# HV_Power_Supply.net
KiCad netlist of a schematic drawn in Altium Designer
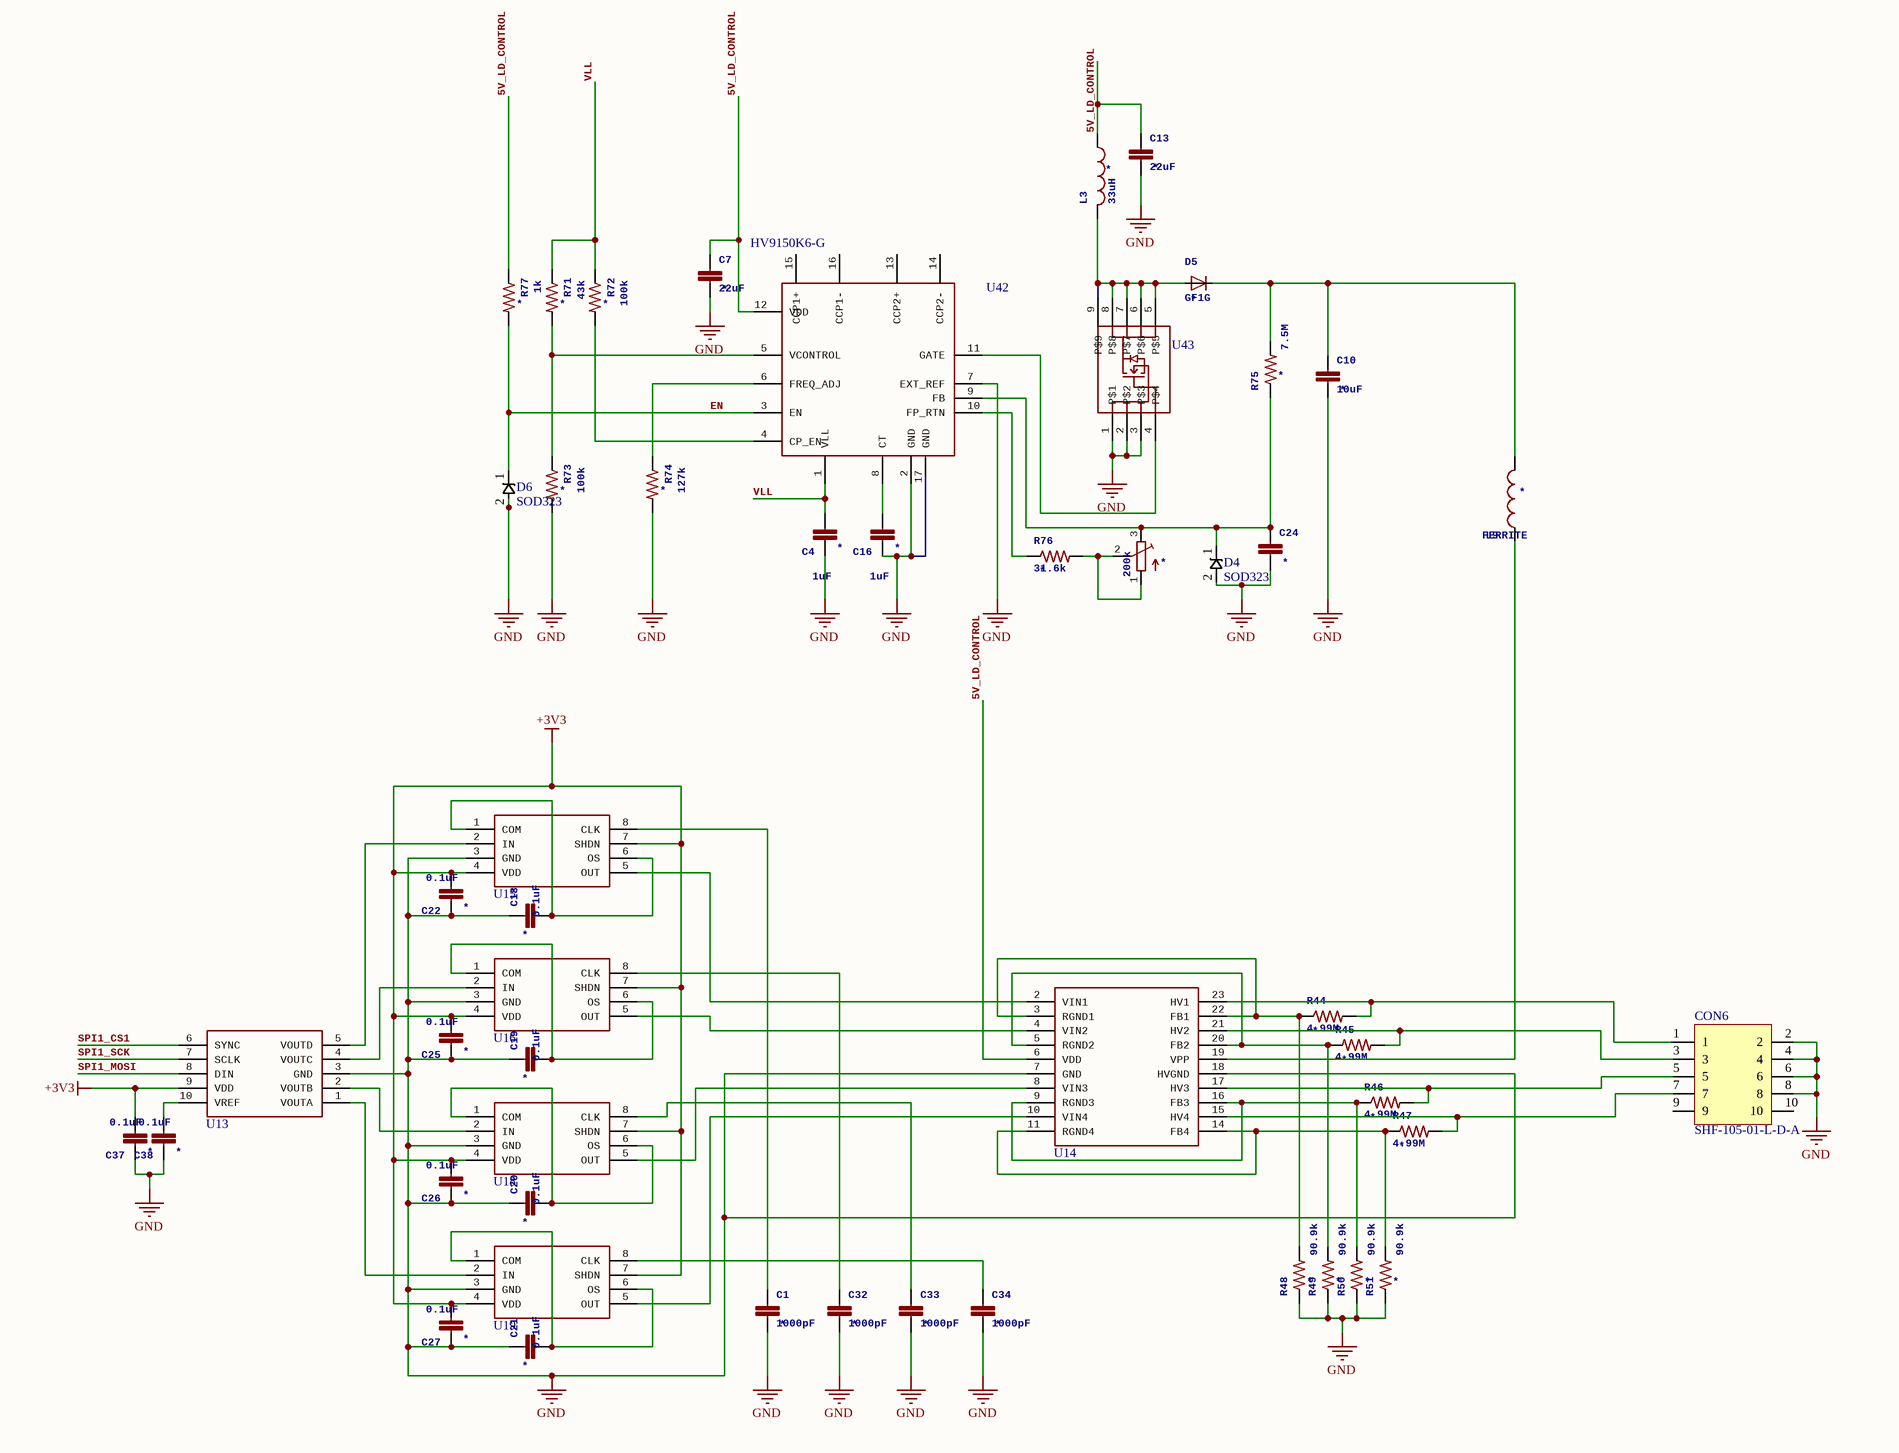
[diagram p0: HV Power Supply.SchDoc]

(export (version "E")
  (design (tool "Eeschema 10.0.6"))
  (components
    (comp (ref "C1")
      (value "1000pF")
      (footprint "0402 B")
      (description "0402 (1005 Metric) Nick Garner - TeleSense")
      (fields (field (name "NAME") "*") (field (name "LIBRARYNAME") "Perfect_0402"))
      (libsource (lib "") (part "CAP_0402_1"))
    )
    (comp (ref "C4")
      (value "1uF")
      (footprint "0603")
      (description "CAPACITOR, European symbol")
      (fields (field (name "NAME") "*"))
      (libsource (lib "") (part "C-EUC0603_1"))
    )
    (comp (ref "C7")
      (value "22uF")
      (footprint "0603")
      (description "CAPACITOR, European symbol")
      (fields (field (name "NAME") "*"))
      (libsource (lib "rcl") (part "C-EUC0603"))
    )
    (comp (ref "C10")
      (value "10uF")
      (footprint "C1812")
      (description "CAPACITOR, European symbol")
      (fields (field (name "NAME") "*"))
      (libsource (lib "rcl") (part "C-EUC1812"))
    )
    (comp (ref "C13")
      (value "22uF")
      (footprint "0603")
      (description "CAPACITOR, European symbol")
      (fields (field (name "NAME") "*"))
      (libsource (lib "rcl") (part "C-EUC0603"))
    )
    (comp (ref "C16")
      (value "1uF")
      (footprint "0603")
      (description "CAPACITOR, European symbol")
      (fields (field (name "NAME") "*"))
      (libsource (lib "") (part "C-EUC0603_1"))
    )
    (comp (ref "C18")
      (value "0.1uF")
      (footprint "0402 B")
      (description "0402 (1005 Metric) Nick Garner - TeleSense")
      (fields (field (name "NAME") "*") (field (name "LIBRARYNAME") "Perfect_0402"))
      (libsource (lib "") (part "CAP_0402_2"))
    )
    (comp (ref "C19")
      (value "0.1uF")
      (footprint "0402 B")
      (description "0402 (1005 Metric) Nick Garner - TeleSense")
      (fields (field (name "NAME") "*") (field (name "LIBRARYNAME") "Perfect_0402"))
      (libsource (lib "") (part "CAP_0402_2"))
    )
    (comp (ref "C20")
      (value "0.1uF")
      (footprint "0402 B")
      (description "0402 (1005 Metric) Nick Garner - TeleSense")
      (fields (field (name "NAME") "*") (field (name "LIBRARYNAME") "Perfect_0402"))
      (libsource (lib "") (part "CAP_0402_2"))
    )
    (comp (ref "C21")
      (value "0.1uF")
      (footprint "0402 B")
      (description "0402 (1005 Metric) Nick Garner - TeleSense")
      (fields (field (name "NAME") "*") (field (name "LIBRARYNAME") "Perfect_0402"))
      (libsource (lib "") (part "CAP_0402_2"))
    )
    (comp (ref "C22")
      (value "0.1uF")
      (footprint "0402 B")
      (description "0402 (1005 Metric) Nick Garner - TeleSense")
      (fields (field (name "NAME") "*") (field (name "LIBRARYNAME") "Perfect_0402"))
      (libsource (lib "Perfect_0402") (part "CAP_0402"))
    )
    (comp (ref "C24")
      (value "C-EUC0603")
      (footprint "0603")
      (description "CAPACITOR, European symbol")
      (fields (field (name "NAME") "*"))
      (libsource (lib "rcl") (part "C-EUC0603"))
    )
    (comp (ref "C25")
      (value "0.1uF")
      (footprint "0402 B")
      (description "0402 (1005 Metric) Nick Garner - TeleSense")
      (fields (field (name "NAME") "*") (field (name "LIBRARYNAME") "Perfect_0402"))
      (libsource (lib "Perfect_0402") (part "CAP_0402"))
    )
    (comp (ref "C26")
      (value "0.1uF")
      (footprint "0402 B")
      (description "0402 (1005 Metric) Nick Garner - TeleSense")
      (fields (field (name "NAME") "*") (field (name "LIBRARYNAME") "Perfect_0402"))
      (libsource (lib "Perfect_0402") (part "CAP_0402"))
    )
    (comp (ref "C27")
      (value "0.1uF")
      (footprint "0402 B")
      (description "0402 (1005 Metric) Nick Garner - TeleSense")
      (fields (field (name "NAME") "*") (field (name "LIBRARYNAME") "Perfect_0402"))
      (libsource (lib "Perfect_0402") (part "CAP_0402"))
    )
    (comp (ref "C32")
      (value "1000pF")
      (footprint "0402 B")
      (description "0402 (1005 Metric) Nick Garner - TeleSense")
      (fields (field (name "NAME") "*") (field (name "LIBRARYNAME") "Perfect_0402"))
      (libsource (lib "") (part "CAP_0402_1"))
    )
    (comp (ref "C33")
      (value "1000pF")
      (footprint "0402 B")
      (description "0402 (1005 Metric) Nick Garner - TeleSense")
      (fields (field (name "NAME") "*") (field (name "LIBRARYNAME") "Perfect_0402"))
      (libsource (lib "") (part "CAP_0402_1"))
    )
    (comp (ref "C34")
      (value "1000pF")
      (footprint "0402 B")
      (description "0402 (1005 Metric) Nick Garner - TeleSense")
      (fields (field (name "NAME") "*") (field (name "LIBRARYNAME") "Perfect_0402"))
      (libsource (lib "") (part "CAP_0402_1"))
    )
    (comp (ref "C37")
      (value "0.1uF")
      (footprint "0402 B")
      (description "0402 (1005 Metric) Nick Garner - TeleSense")
      (fields (field (name "NAME") "*") (field (name "LIBRARYNAME") "Perfect_0402"))
      (libsource (lib "Perfect_0402") (part "CAP_0402"))
    )
    (comp (ref "C38")
      (value "0.1uF")
      (footprint "0402 B")
      (description "0402 (1005 Metric) Nick Garner - TeleSense")
      (fields (field (name "NAME") "*") (field (name "LIBRARYNAME") "Perfect_0402"))
      (libsource (lib "Perfect_0402") (part "CAP_0402"))
    )
    (comp (ref "CON6")
      (value "SHF-105-01-L-D-A")
      (footprint "SHF-105-01-L-D-RA")
      (libsource (lib "DaughterBoard") (part "SHF-105-01-L-D-A"))
    )
    (comp (ref "D4") (value "SOD323") (footprint "SOD-323") (libsource (lib "DaughterBoard") (part "SOD323")))
    (comp (ref "D5")
      (value "GF1G")
      (footprint "DO-214BA")
      (description "DIODE")
      (fields (field (name "NAME") "*"))
      (libsource (lib "diode") (part "GF1"))
    )
    (comp (ref "D6") (value "SOD323") (footprint "SOD-323") (libsource (lib "DaughterBoard") (part "SOD323")))
    (comp (ref "L3")
      (value "33uH")
      (footprint "L1812")
      (description "INDUCTOR, American symbol")
      (fields (field (name "NAME") "*"))
      (libsource (lib "resistor") (part "L-USL1812"))
    )
    (comp (ref "L9")
      (value "FERRITE")
      (footprint "0603")
      (fields (field (name "NAME") "*"))
      (libsource (lib "SparkFun-Passives") (part "INDUCTOR30OHM,1.8A"))
    )
    (comp (ref "R44")
      (value "4.99M")
      (footprint "0603R")
      (description "RESISTOR, American symbol")
      (fields (field (name "NAME") "*"))
      (libsource (lib "rcl") (part "R-US_R0603"))
    )
    (comp (ref "R45")
      (value "4.99M")
      (footprint "0603R")
      (description "RESISTOR, American symbol")
      (fields (field (name "NAME") "*"))
      (libsource (lib "rcl") (part "R-US_R0603"))
    )
    (comp (ref "R46")
      (value "4.99M")
      (footprint "0603R")
      (description "RESISTOR, American symbol")
      (fields (field (name "NAME") "*"))
      (libsource (lib "rcl") (part "R-US_R0603"))
    )
    (comp (ref "R47")
      (value "4.99M")
      (footprint "0603R")
      (description "RESISTOR, American symbol")
      (fields (field (name "NAME") "*"))
      (libsource (lib "rcl") (part "R-US_R0603"))
    )
    (comp (ref "R48")
      (value "90.9k")
      (footprint "0603R")
      (description "RESISTOR, American symbol")
      (fields (field (name "NAME") "*"))
      (libsource (lib "rcl") (part "R-US_R0603"))
    )
    (comp (ref "R49")
      (value "90.9k")
      (footprint "0603R")
      (description "RESISTOR, American symbol")
      (fields (field (name "NAME") "*"))
      (libsource (lib "rcl") (part "R-US_R0603"))
    )
    (comp (ref "R50")
      (value "90.9k")
      (footprint "0603R")
      (description "RESISTOR, American symbol")
      (fields (field (name "NAME") "*"))
      (libsource (lib "rcl") (part "R-US_R0603"))
    )
    (comp (ref "R51")
      (value "90.9k")
      (footprint "0603R")
      (description "RESISTOR, American symbol")
      (fields (field (name "NAME") "*"))
      (libsource (lib "rcl") (part "R-US_R0603"))
    )
    (comp (ref "R71")
      (value "43k")
      (footprint "0603R")
      (description "RESISTOR, American symbol")
      (fields (field (name "NAME") "*"))
      (libsource (lib "rcl") (part "R-US_R0603"))
    )
    (comp (ref "R72")
      (value "100k")
      (footprint "0603R")
      (description "RESISTOR, American symbol")
      (fields (field (name "NAME") "*"))
      (libsource (lib "rcl") (part "R-US_R0603"))
    )
    (comp (ref "R73")
      (value "100k")
      (footprint "0603R")
      (description "RESISTOR, American symbol")
      (fields (field (name "NAME") "*"))
      (libsource (lib "rcl") (part "R-US_R0603"))
    )
    (comp (ref "R74")
      (value "127k")
      (footprint "0603R")
      (description "RESISTOR, American symbol")
      (fields (field (name "NAME") "*"))
      (libsource (lib "rcl") (part "R-US_R0603"))
    )
    (comp (ref "R75")
      (value "7.5M")
      (footprint "1206R")
      (description "RESISTOR, American symbol")
      (fields (field (name "NAME") "*"))
      (libsource (lib "rcl") (part "R-US_R1206"))
    )
    (comp (ref "R76")
      (value "31.6k")
      (footprint "0603R")
      (description "RESISTOR, American symbol")
      (fields (field (name "NAME") "*"))
      (libsource (lib "rcl") (part "R-US_R0603"))
    )
    (comp (ref "R77")
      (value "1k")
      (footprint "0603R")
      (description "RESISTOR, American symbol")
      (fields (field (name "NAME") "*"))
      (libsource (lib "rcl") (part "R-US_R0603"))
    )
    (comp (ref "U13") (value "AD5664R") (footprint "MSOP-10") (libsource (lib "custom") (part "AD5664R")))
    (comp (ref "U14") (value "HV264TS-G") (footprint "TSSOP-24") (libsource (lib "custom") (part "HV264")))
    (comp (ref "U15") (value "MAX7413") (footprint "uMAX-8") (libsource (lib "custom") (part "MAX7413")))
    (comp (ref "U16") (value "MAX7413") (footprint "uMAX-8") (libsource (lib "custom") (part "MAX7413")))
    (comp (ref "U18") (value "MAX7413") (footprint "uMAX-8") (libsource (lib "custom") (part "MAX7413")))
    (comp (ref "U19") (value "MAX7413") (footprint "uMAX-8") (libsource (lib "custom") (part "MAX7413")))
    (comp (ref "U42") (value "HV9150K6-G") (footprint "QFN-16") (libsource (lib "custom") (part "HV9150")))
    (comp (ref "U43")
      (value "BSZ42DN25NS3GATMA1")
      (footprint "TDSON-8")
      (libsource (lib "custom") (part "BSZ42DN25NS3"))
    )
    (comp (ref "U44")
      (value "200k")
      (footprint "TC33X")
      (description "SMT trimmer potentiometer part number TC33X http://www.ladyada.net/library/eagle")
      (fields (field (name "NAME") "*"))
      (libsource (lib "adafruit") (part "TRIMPOTTC33X"))
    )
  )
  (nets
    (net (code "1") (name "+3V3") (class "Default")
      (node (ref "C22") (pin "2") (pinfunction "2_2") (pintype "passive"))
      (node (ref "C25") (pin "2") (pinfunction "2_2") (pintype "passive"))
      (node (ref "C26") (pin "2") (pinfunction "2_2") (pintype "passive"))
      (node (ref "C27") (pin "2") (pinfunction "2_2") (pintype "passive"))
      (node (ref "C37") (pin "2") (pinfunction "2_2") (pintype "passive"))
      (node (ref "U13") (pin "9") (pinfunction "VDD_9") (pintype "passive"))
      (node (ref "U15") (pin "4") (pinfunction "VDD_4") (pintype "passive"))
      (node (ref "U15") (pin "7") (pinfunction "SHDN_7") (pintype "passive"))
      (node (ref "U16") (pin "4") (pinfunction "VDD_4") (pintype "passive"))
      (node (ref "U16") (pin "7") (pinfunction "SHDN_7") (pintype "passive"))
      (node (ref "U18") (pin "4") (pinfunction "VDD_4") (pintype "passive"))
      (node (ref "U18") (pin "7") (pinfunction "SHDN_7") (pintype "passive"))
      (node (ref "U19") (pin "4") (pinfunction "VDD_4") (pintype "passive"))
      (node (ref "U19") (pin "7") (pinfunction "SHDN_7") (pintype "passive"))
    )
    (net (code "2") (name "/5V_LD_CONTROL") (class "Default")
      (node (ref "C13") (pin "1") (pinfunction "1_1") (pintype "passive"))
      (node (ref "C7") (pin "1") (pinfunction "1_1") (pintype "passive"))
      (node (ref "L3") (pin "1") (pinfunction "1_1") (pintype "passive"))
      (node (ref "R77") (pin "1") (pinfunction "1_1") (pintype "passive"))
      (node (ref "U14") (pin "6") (pinfunction "VDD_6") (pintype "passive"))
      (node (ref "U42") (pin "12") (pinfunction "VDD_12") (pintype "passive"))
    )
    (net (code "3") (name "/EN") (class "Default")
      (node (ref "D6") (pin "1") (pinfunction "31_1") (pintype "passive"))
      (node (ref "R77") (pin "2") (pinfunction "2_2") (pintype "passive"))
      (node (ref "U42") (pin "3") (pinfunction "EN_3") (pintype "passive"))
    )
    (net (code "4") (name "/SPI1_CS1") (class "Default")
      (node (ref "U13") (pin "6") (pinfunction "SYNC_6") (pintype "passive"))
    )
    (net (code "5") (name "/SPI1_MOSI") (class "Default")
      (node (ref "U13") (pin "8") (pinfunction "DIN_8") (pintype "passive"))
    )
    (net (code "6") (name "/SPI1_SCK") (class "Default")
      (node (ref "U13") (pin "7") (pinfunction "SCLK_7") (pintype "passive"))
    )
    (net (code "7") (name "/VLL") (class "Default")
      (node (ref "C4") (pin "2") (pinfunction "2_2") (pintype "passive"))
      (node (ref "R71") (pin "1") (pinfunction "1_1") (pintype "passive"))
      (node (ref "R72") (pin "1") (pinfunction "1_1") (pintype "passive"))
      (node (ref "U42") (pin "1") (pinfunction "VLL_1") (pintype "passive"))
    )
    (net (code "8") (name "GND") (class "Default")
      (node (ref "C1") (pin "2") (pinfunction "2_2") (pintype "passive"))
      (node (ref "C10") (pin "2") (pinfunction "2_2") (pintype "passive"))
      (node (ref "C13") (pin "2") (pinfunction "2_2") (pintype "passive"))
      (node (ref "C16") (pin "1") (pinfunction "1_1") (pintype "passive"))
      (node (ref "C18") (pin "1") (pinfunction "1_1") (pintype "passive"))
      (node (ref "C19") (pin "1") (pinfunction "1_1") (pintype "passive"))
      (node (ref "C20") (pin "1") (pinfunction "1_1") (pintype "passive"))
      (node (ref "C21") (pin "1") (pinfunction "1_1") (pintype "passive"))
      (node (ref "C22") (pin "1") (pinfunction "1_1") (pintype "passive"))
      (node (ref "C24") (pin "2") (pinfunction "2_2") (pintype "passive"))
      (node (ref "C25") (pin "1") (pinfunction "1_1") (pintype "passive"))
      (node (ref "C26") (pin "1") (pinfunction "1_1") (pintype "passive"))
      (node (ref "C27") (pin "1") (pinfunction "1_1") (pintype "passive"))
      (node (ref "C32") (pin "2") (pinfunction "2_2") (pintype "passive"))
      (node (ref "C33") (pin "2") (pinfunction "2_2") (pintype "passive"))
      (node (ref "C34") (pin "2") (pinfunction "2_2") (pintype "passive"))
      (node (ref "C37") (pin "1") (pinfunction "1_1") (pintype "passive"))
      (node (ref "C38") (pin "1") (pinfunction "1_1") (pintype "passive"))
      (node (ref "C4") (pin "1") (pinfunction "1_1") (pintype "passive"))
      (node (ref "C7") (pin "2") (pinfunction "2_2") (pintype "passive"))
      (node (ref "CON6") (pin "2") (pinfunction "2_2") (pintype "passive"))
      (node (ref "CON6") (pin "4") (pinfunction "4_4") (pintype "passive"))
      (node (ref "CON6") (pin "6") (pinfunction "6_6") (pintype "passive"))
      (node (ref "CON6") (pin "8") (pinfunction "8_8") (pintype "passive"))
      (node (ref "D4") (pin "2") (pinfunction "32_2") (pintype "passive"))
      (node (ref "D6") (pin "2") (pinfunction "32_2") (pintype "passive"))
      (node (ref "R48") (pin "1") (pinfunction "1_1") (pintype "passive"))
      (node (ref "R49") (pin "1") (pinfunction "1_1") (pintype "passive"))
      (node (ref "R50") (pin "1") (pinfunction "1_1") (pintype "passive"))
      (node (ref "R51") (pin "1") (pinfunction "1_1") (pintype "passive"))
      (node (ref "R73") (pin "2") (pinfunction "2_2") (pintype "passive"))
      (node (ref "R74") (pin "2") (pinfunction "2_2") (pintype "passive"))
      (node (ref "U13") (pin "3") (pinfunction "GND_3") (pintype "passive"))
      (node (ref "U14") (pin "18") (pinfunction "HVGND_18") (pintype "passive"))
      (node (ref "U14") (pin "7") (pinfunction "GND_7") (pintype "passive"))
      (node (ref "U15") (pin "3") (pinfunction "GND_3") (pintype "passive"))
      (node (ref "U16") (pin "3") (pinfunction "GND_3") (pintype "passive"))
      (node (ref "U18") (pin "3") (pinfunction "GND_3") (pintype "passive"))
      (node (ref "U19") (pin "3") (pinfunction "GND_3") (pintype "passive"))
      (node (ref "U42") (pin "17") (pinfunction "GND_17") (pintype "passive"))
      (node (ref "U42") (pin "2") (pinfunction "GND_2") (pintype "passive"))
      (node (ref "U42") (pin "7") (pinfunction "EXT_REF_7") (pintype "passive"))
      (node (ref "U43") (pin "1") (pinfunction "P$1_1") (pintype "passive"))
      (node (ref "U43") (pin "2") (pinfunction "P$2_2") (pintype "passive"))
      (node (ref "U43") (pin "3") (pinfunction "P$3_3") (pintype "passive"))
    )
    (net (code "9") (name "Net-(C10-Pad1)") (class "Default")
      (node (ref "C10") (pin "1") (pinfunction "1_1") (pintype "passive"))
      (node (ref "D5") (pin "2") (pinfunction "2_2") (pintype "passive"))
      (node (ref "L9") (pin "2") (pinfunction "2_2") (pintype "passive"))
      (node (ref "R75") (pin "2") (pinfunction "2_2") (pintype "passive"))
    )
    (net (code "10") (name "Net-(D4-31)") (class "Default")
      (node (ref "C24") (pin "1") (pinfunction "1_1") (pintype "passive"))
      (node (ref "D4") (pin "1") (pinfunction "31_1") (pintype "passive"))
      (node (ref "R75") (pin "1") (pinfunction "1_1") (pintype "passive"))
      (node (ref "U42") (pin "9") (pinfunction "FB_9") (pintype "passive"))
      (node (ref "U44") (pin "3") (pinfunction "E_3") (pintype "passive"))
    )
    (net (code "11") (name "Net-(U13-VOUTA)") (class "Default")
      (node (ref "U13") (pin "1") (pinfunction "VOUTA_1") (pintype "passive"))
      (node (ref "U19") (pin "2") (pinfunction "IN_2") (pintype "passive"))
    )
    (net (code "12") (name "Net-(U13-VOUTB)") (class "Default")
      (node (ref "U13") (pin "2") (pinfunction "VOUTB_2") (pintype "passive"))
      (node (ref "U18") (pin "2") (pinfunction "IN_2") (pintype "passive"))
    )
    (net (code "13") (name "Net-(U13-VOUTC)") (class "Default")
      (node (ref "U13") (pin "4") (pinfunction "VOUTC_4") (pintype "passive"))
      (node (ref "U16") (pin "2") (pinfunction "IN_2") (pintype "passive"))
    )
    (net (code "14") (name "Net-(U13-VOUTD)") (class "Default")
      (node (ref "U13") (pin "5") (pinfunction "VOUTD_5") (pintype "passive"))
      (node (ref "U15") (pin "2") (pinfunction "IN_2") (pintype "passive"))
    )
    (net (code "15") (name "Net-(U13-VREF)") (class "Default")
      (node (ref "C38") (pin "2") (pinfunction "2_2") (pintype "passive"))
      (node (ref "U13") (pin "10") (pinfunction "VREF_10") (pintype "passive"))
    )
    (net (code "16") (name "Net-(U14-FB1)") (class "Default")
      (node (ref "R44") (pin "1") (pinfunction "1_1") (pintype "passive"))
      (node (ref "R48") (pin "2") (pinfunction "2_2") (pintype "passive"))
      (node (ref "U14") (pin "22") (pinfunction "FB1_22") (pintype "passive"))
      (node (ref "U14") (pin "3") (pinfunction "RGND1_3") (pintype "passive"))
    )
    (net (code "17") (name "Net-(U14-FB2)") (class "Default")
      (node (ref "R45") (pin "1") (pinfunction "1_1") (pintype "passive"))
      (node (ref "R49") (pin "2") (pinfunction "2_2") (pintype "passive"))
      (node (ref "U14") (pin "20") (pinfunction "FB2_20") (pintype "passive"))
      (node (ref "U14") (pin "5") (pinfunction "RGND2_5") (pintype "passive"))
    )
    (net (code "18") (name "Net-(U14-FB3)") (class "Default")
      (node (ref "R46") (pin "1") (pinfunction "1_1") (pintype "passive"))
      (node (ref "R50") (pin "2") (pinfunction "2_2") (pintype "passive"))
      (node (ref "U14") (pin "16") (pinfunction "FB3_16") (pintype "passive"))
      (node (ref "U14") (pin "9") (pinfunction "RGND3_9") (pintype "passive"))
    )
    (net (code "19") (name "Net-(U14-FB4)") (class "Default")
      (node (ref "R47") (pin "1") (pinfunction "1_1") (pintype "passive"))
      (node (ref "R51") (pin "2") (pinfunction "2_2") (pintype "passive"))
      (node (ref "U14") (pin "11") (pinfunction "RGND4_11") (pintype "passive"))
      (node (ref "U14") (pin "14") (pinfunction "FB4_14") (pintype "passive"))
    )
    (net (code "20") (name "Net-(U14-HV1)") (class "Default")
      (node (ref "CON6") (pin "1") (pinfunction "1_1") (pintype "passive"))
      (node (ref "R44") (pin "2") (pinfunction "2_2") (pintype "passive"))
      (node (ref "U14") (pin "23") (pinfunction "HV1_23") (pintype "passive"))
    )
    (net (code "21") (name "Net-(U14-HV2)") (class "Default")
      (node (ref "CON6") (pin "3") (pinfunction "3_3") (pintype "passive"))
      (node (ref "R45") (pin "2") (pinfunction "2_2") (pintype "passive"))
      (node (ref "U14") (pin "21") (pinfunction "HV2_21") (pintype "passive"))
    )
    (net (code "22") (name "Net-(U14-HV3)") (class "Default")
      (node (ref "CON6") (pin "5") (pinfunction "5_5") (pintype "passive"))
      (node (ref "R46") (pin "2") (pinfunction "2_2") (pintype "passive"))
      (node (ref "U14") (pin "17") (pinfunction "HV3_17") (pintype "passive"))
    )
    (net (code "23") (name "Net-(U14-HV4)") (class "Default")
      (node (ref "CON6") (pin "7") (pinfunction "7_7") (pintype "passive"))
      (node (ref "R47") (pin "2") (pinfunction "2_2") (pintype "passive"))
      (node (ref "U14") (pin "15") (pinfunction "HV4_15") (pintype "passive"))
    )
    (net (code "24") (name "Net-(U14-VIN1)") (class "Default")
      (node (ref "U14") (pin "2") (pinfunction "VIN1_2") (pintype "passive"))
      (node (ref "U15") (pin "5") (pinfunction "OUT_5") (pintype "passive"))
    )
    (net (code "25") (name "Net-(U14-VIN2)") (class "Default")
      (node (ref "U14") (pin "4") (pinfunction "VIN2_4") (pintype "passive"))
      (node (ref "U16") (pin "5") (pinfunction "OUT_5") (pintype "passive"))
    )
    (net (code "26") (name "Net-(U14-VIN3)") (class "Default")
      (node (ref "U14") (pin "8") (pinfunction "VIN3_8") (pintype "passive"))
      (node (ref "U18") (pin "5") (pinfunction "OUT_5") (pintype "passive"))
    )
    (net (code "27") (name "Net-(U14-VIN4)") (class "Default")
      (node (ref "U14") (pin "10") (pinfunction "VIN4_10") (pintype "passive"))
      (node (ref "U19") (pin "5") (pinfunction "OUT_5") (pintype "passive"))
    )
    (net (code "28") (name "Net-(U14-VPP)") (class "Default")
      (node (ref "L9") (pin "1") (pinfunction "1_1") (pintype "passive"))
      (node (ref "U14") (pin "19") (pinfunction "VPP_19") (pintype "passive"))
    )
    (net (code "29") (name "Net-(U15-CLK)") (class "Default")
      (node (ref "C1") (pin "1") (pinfunction "1_1") (pintype "passive"))
      (node (ref "U15") (pin "8") (pinfunction "CLK_8") (pintype "passive"))
    )
    (net (code "30") (name "Net-(U15-COM)") (class "Default")
      (node (ref "C18") (pin "2") (pinfunction "2_2") (pintype "passive"))
      (node (ref "U15") (pin "1") (pinfunction "COM_1") (pintype "passive"))
      (node (ref "U15") (pin "6") (pinfunction "OS_6") (pintype "passive"))
    )
    (net (code "31") (name "Net-(U16-CLK)") (class "Default")
      (node (ref "C32") (pin "1") (pinfunction "1_1") (pintype "passive"))
      (node (ref "U16") (pin "8") (pinfunction "CLK_8") (pintype "passive"))
    )
    (net (code "32") (name "Net-(U16-COM)") (class "Default")
      (node (ref "C19") (pin "2") (pinfunction "2_2") (pintype "passive"))
      (node (ref "U16") (pin "1") (pinfunction "COM_1") (pintype "passive"))
      (node (ref "U16") (pin "6") (pinfunction "OS_6") (pintype "passive"))
    )
    (net (code "33") (name "Net-(U18-CLK)") (class "Default")
      (node (ref "C33") (pin "1") (pinfunction "1_1") (pintype "passive"))
      (node (ref "U18") (pin "8") (pinfunction "CLK_8") (pintype "passive"))
    )
    (net (code "34") (name "Net-(U18-COM)") (class "Default")
      (node (ref "C20") (pin "2") (pinfunction "2_2") (pintype "passive"))
      (node (ref "U18") (pin "1") (pinfunction "COM_1") (pintype "passive"))
      (node (ref "U18") (pin "6") (pinfunction "OS_6") (pintype "passive"))
    )
    (net (code "35") (name "Net-(U19-CLK)") (class "Default")
      (node (ref "C34") (pin "1") (pinfunction "1_1") (pintype "passive"))
      (node (ref "U19") (pin "8") (pinfunction "CLK_8") (pintype "passive"))
    )
    (net (code "36") (name "Net-(U19-COM)") (class "Default")
      (node (ref "C21") (pin "2") (pinfunction "2_2") (pintype "passive"))
      (node (ref "U19") (pin "1") (pinfunction "COM_1") (pintype "passive"))
      (node (ref "U19") (pin "6") (pinfunction "OS_6") (pintype "passive"))
    )
    (net (code "37") (name "Net-(U42-CP_EN)") (class "Default")
      (node (ref "R72") (pin "2") (pinfunction "2_2") (pintype "passive"))
      (node (ref "U42") (pin "4") (pinfunction "CP_EN_4") (pintype "passive"))
    )
    (net (code "38") (name "Net-(U42-CT)") (class "Default")
      (node (ref "C16") (pin "2") (pinfunction "2_2") (pintype "passive"))
      (node (ref "U42") (pin "8") (pinfunction "CT_8") (pintype "passive"))
    )
    (net (code "39") (name "Net-(U42-FP_RTN)") (class "Default")
      (node (ref "R76") (pin "1") (pinfunction "1_1") (pintype "passive"))
      (node (ref "U42") (pin "10") (pinfunction "FP_RTN_10") (pintype "passive"))
    )
    (net (code "40") (name "Net-(U42-FREQ_ADJ)") (class "Default")
      (node (ref "R74") (pin "1") (pinfunction "1_1") (pintype "passive"))
      (node (ref "U42") (pin "6") (pinfunction "FREQ_ADJ_6") (pintype "passive"))
    )
    (net (code "41") (name "Net-(U42-GATE)") (class "Default")
      (node (ref "U42") (pin "11") (pinfunction "GATE_11") (pintype "passive"))
      (node (ref "U43") (pin "4") (pinfunction "P$4_4") (pintype "passive"))
    )
    (net (code "42") (name "Net-(U42-VCONTROL)") (class "Default")
      (node (ref "R71") (pin "2") (pinfunction "2_2") (pintype "passive"))
      (node (ref "R73") (pin "1") (pinfunction "1_1") (pintype "passive"))
      (node (ref "U42") (pin "5") (pinfunction "VCONTROL_5") (pintype "passive"))
    )
    (net (code "43") (name "Net-(U43-P$5)") (class "Default")
      (node (ref "D5") (pin "1") (pinfunction "1_1") (pintype "passive"))
      (node (ref "L3") (pin "2") (pinfunction "2_2") (pintype "passive"))
      (node (ref "U43") (pin "5") (pinfunction "P$5_5") (pintype "passive"))
      (node (ref "U43") (pin "6") (pinfunction "P$6_6") (pintype "passive"))
      (node (ref "U43") (pin "7") (pinfunction "P$7_7") (pintype "passive"))
      (node (ref "U43") (pin "8") (pinfunction "P$8_8") (pintype "passive"))
      (node (ref "U43") (pin "9") (pinfunction "P$9_9") (pintype "passive"))
    )
    (net (code "44") (name "Net-(U44-A)") (class "Default")
      (node (ref "R76") (pin "2") (pinfunction "2_2") (pintype "passive"))
      (node (ref "U44") (pin "1") (pinfunction "A_1") (pintype "passive"))
      (node (ref "U44") (pin "2") (pinfunction "S_2") (pintype "passive"))
    )
    (net (code "45") (name "unconnected-(CON6-Pad9)") (class "Default")
      (node (ref "CON6") (pin "9") (pinfunction "9_9") (pintype "passive"))
    )
    (net (code "46") (name "unconnected-(CON6-Pad10)") (class "Default")
      (node (ref "CON6") (pin "10") (pinfunction "10_10") (pintype "passive"))
    )
    (net (code "47") (name "unconnected-(U42-CCP1+-Pad15)") (class "Default")
      (node (ref "U42") (pin "15") (pinfunction "CCP1+_15") (pintype "passive"))
    )
    (net (code "48") (name "unconnected-(U42-CCP1--Pad16)") (class "Default")
      (node (ref "U42") (pin "16") (pinfunction "CCP1-_16") (pintype "passive"))
    )
    (net (code "49") (name "unconnected-(U42-CCP2+-Pad13)") (class "Default")
      (node (ref "U42") (pin "13") (pinfunction "CCP2+_13") (pintype "passive"))
    )
    (net (code "50") (name "unconnected-(U42-CCP2--Pad14)") (class "Default")
      (node (ref "U42") (pin "14") (pinfunction "CCP2-_14") (pintype "passive"))
    )
  )
)
